# Midi.net
KiCad netlist of a schematic drawn in Altium Designer
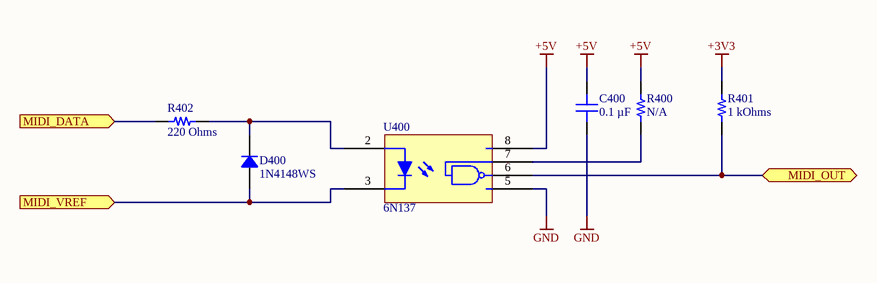
[diagram p0: Midi.SchDoc]

(export (version "E")
  (design (tool "Eeschema 10.0.6"))
  (components
    (comp (ref "C400")
      (value "0.1 µF")
      (footprint "CAP 0603_1608")
      (description "CAP CER 0.1UF 25V Y5V 0603")
      (fields (field (name "PART NUMBER") "CC0603MRY5V8BB104") (field (name "MANUFACTURER") "Yageo"))
      (libsource (lib "Celestial Altium Library") (part "Capacitor"))
    )
    (comp (ref "D400")
      (value "1N4148WS")
      (footprint "SOD323F")
      (description "DIODE GEN PURP 75V 150MA SOD323F")
      (fields (field (name "MANUFACTURER") "ON Semiconductor"))
      (libsource (lib "Celestial Altium Library") (part "Diode"))
    )
    (comp (ref "R400")
      (value "N/A")
      (footprint "RES 0603_1608")
      (description "RESA-AS 0603 10K 1% 100MW TC100")
      (fields (field (name "PART NUMBER") "CR0603AFX-1002EAS") (field (name "MANUFACTURER") "Bourns Inc."))
      (libsource (lib "Celestial Altium Library") (part "Resistor"))
    )
    (comp (ref "R401")
      (value "1 kOhms")
      (footprint "RES 0603_1608")
      (description "RES SMD 1K OHM 1% 1/10W 0603")
      (fields (field (name "PART NUMBER") "CRCW06031K00FKEB") (field (name "MANUFACTURER") "Vishay Dale"))
      (libsource (lib "Celestial Altium Library") (part "Resistor"))
    )
    (comp (ref "R402")
      (value "220 Ohms")
      (footprint "RES 0603_1608")
      (description "RES 220 OHM 1% 1/10W 0603")
      (fields (field (name "PART NUMBER") "CRCW0603220RFKEAC") (field (name "MANUFACTURER") "Vishay Dale"))
      (libsource (lib "Celestial Altium Library") (part "Resistor"))
    )
    (comp (ref "U400")
      (value "6N137")
      (footprint "SMD-8")
      (description "High Speed Single Optocoupler, 10 MBd")
      (libsource (lib "LabratsSynthLib") (part "6N137"))
    )
  )
  (nets
    (net (code "1") (name "+3V3") (class "Default")
      (node (ref "R401") (pin "2") (pinfunction "2_2") (pintype "passive"))
    )
    (net (code "2") (name "+5V") (class "Default")
      (node (ref "C400") (pin "2") (pinfunction "2_2") (pintype "passive"))
      (node (ref "R400") (pin "2") (pinfunction "2_2") (pintype "passive"))
      (node (ref "U400") (pin "8") (pinfunction "VCC_8") (pintype "passive"))
    )
    (net (code "3") (name "/MIDI_DATA") (class "Default")
      (node (ref "R402") (pin "1") (pinfunction "1_1") (pintype "passive"))
    )
    (net (code "4") (name "/MIDI_OUT") (class "Default")
      (node (ref "R401") (pin "1") (pinfunction "1_1") (pintype "passive"))
      (node (ref "U400") (pin "6") (pinfunction "Vout_6") (pintype "passive"))
    )
    (net (code "5") (name "/MIDI_VREF") (class "Default")
      (node (ref "D400") (pin "1") (pinfunction "1_1") (pintype "passive"))
      (node (ref "U400") (pin "3") (pinfunction "Cathode_3") (pintype "passive"))
    )
    (net (code "6") (name "GND") (class "Default")
      (node (ref "C400") (pin "1") (pinfunction "1_1") (pintype "passive"))
      (node (ref "U400") (pin "5") (pinfunction "Gnd_5") (pintype "passive"))
    )
    (net (code "7") (name "Net-(U400-Anode)") (class "Default")
      (node (ref "D400") (pin "2") (pinfunction "2_2") (pintype "passive"))
      (node (ref "R402") (pin "2") (pinfunction "2_2") (pintype "passive"))
      (node (ref "U400") (pin "2") (pinfunction "Anode_2") (pintype "passive"))
    )
    (net (code "8") (name "Net-(U400-VE)") (class "Default")
      (node (ref "R400") (pin "1") (pinfunction "1_1") (pintype "passive"))
      (node (ref "U400") (pin "7") (pinfunction "VE_7") (pintype "passive"))
    )
  )
)
